# pich.net
KiCad netlist of a schematic drawn in EAGLE
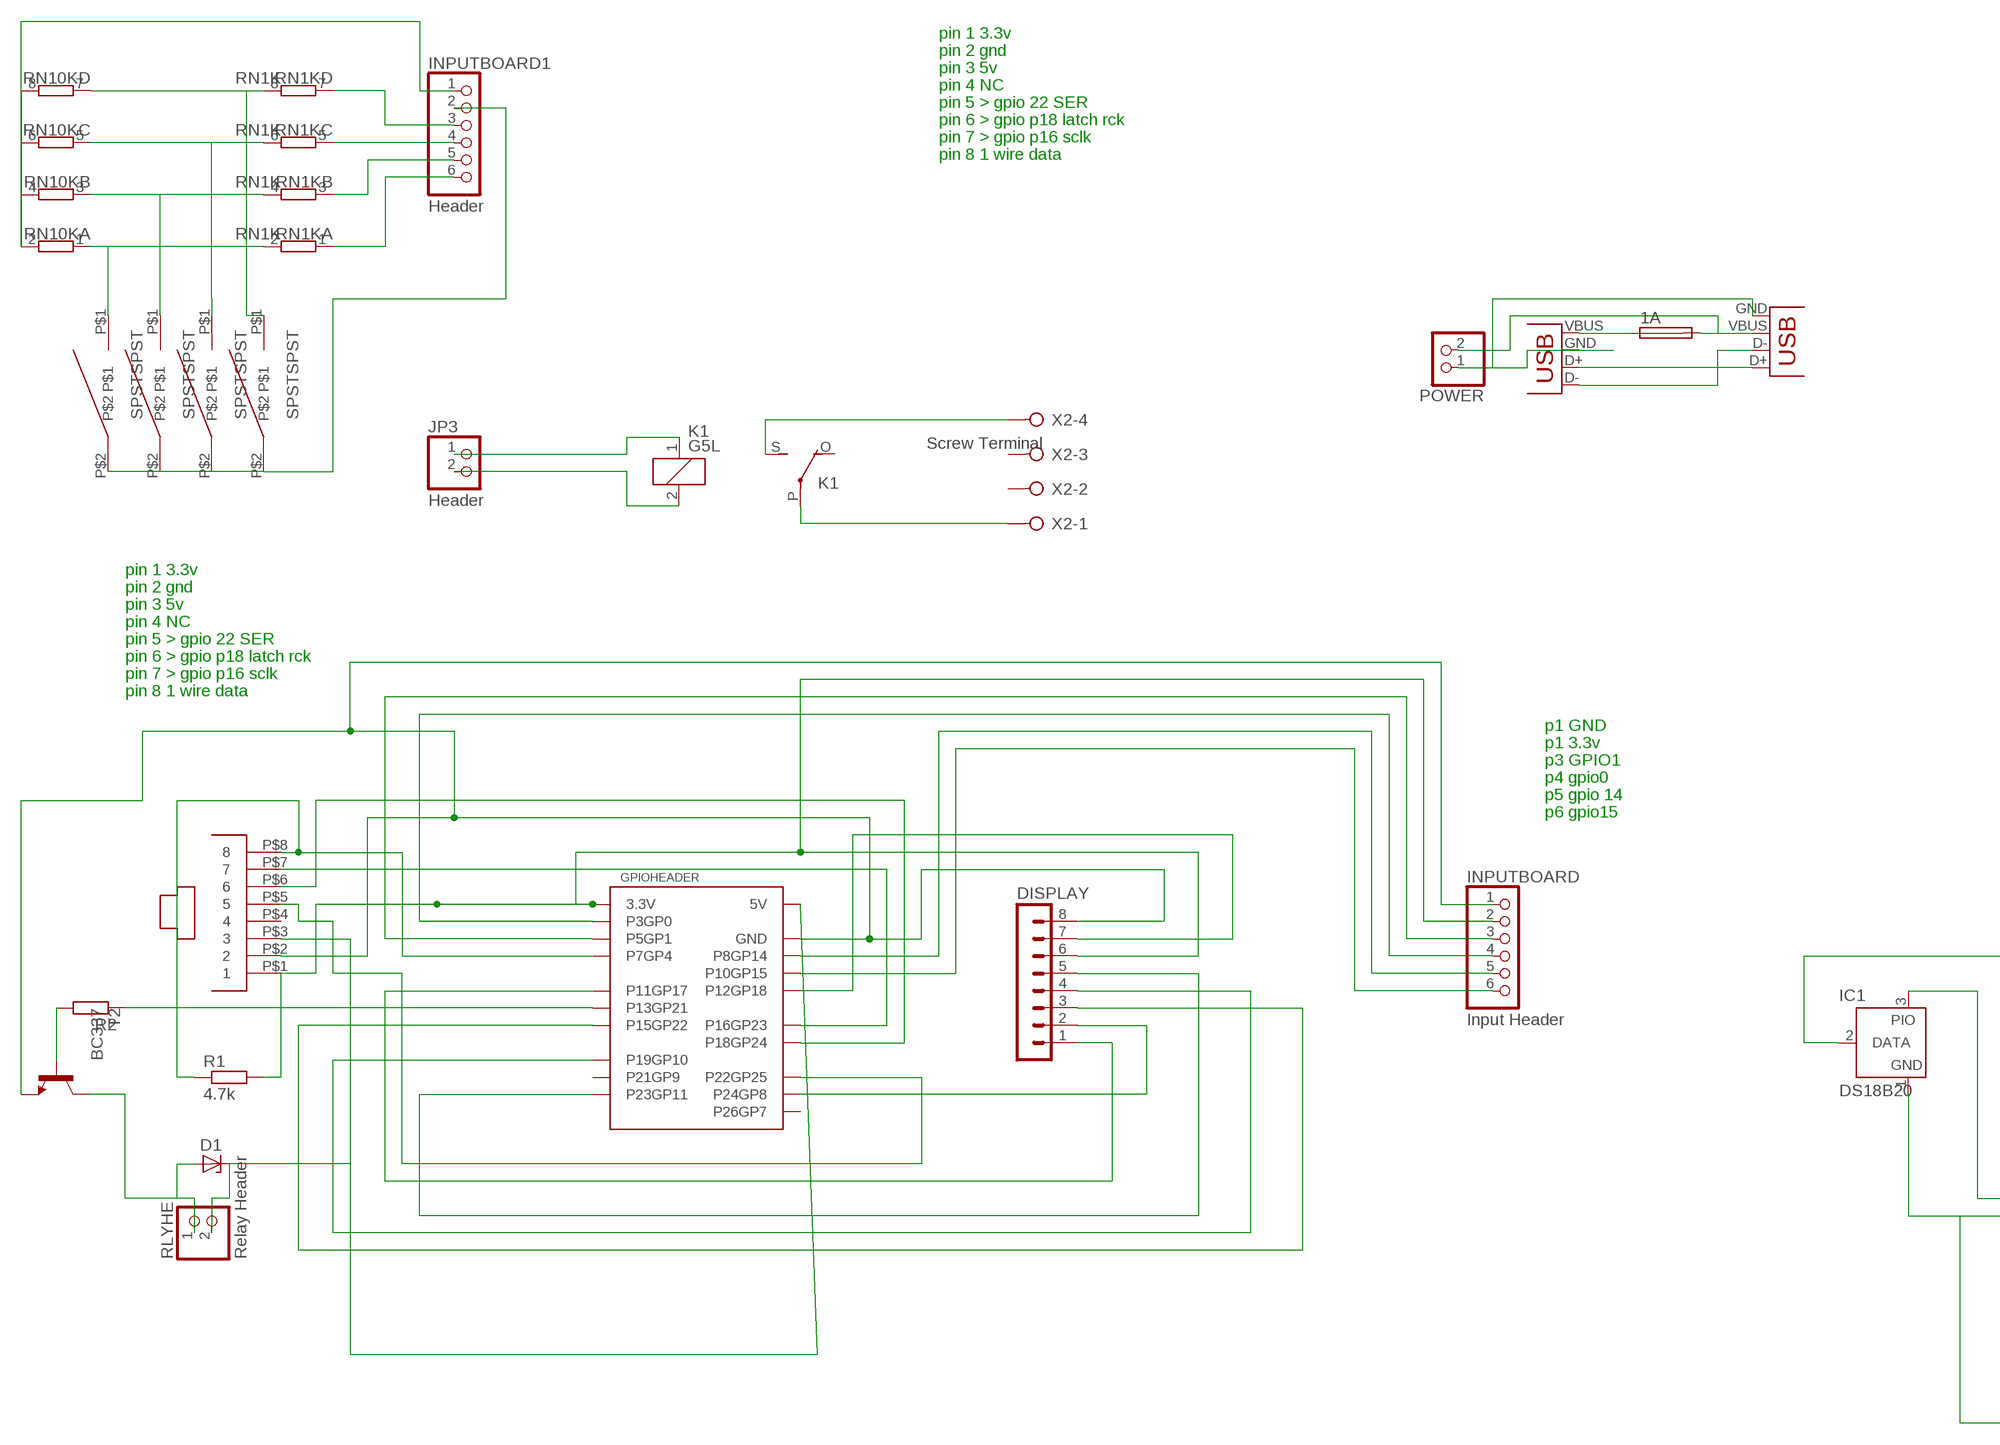
[diagram p0: schematic, sheet 1, part 1 of 2]
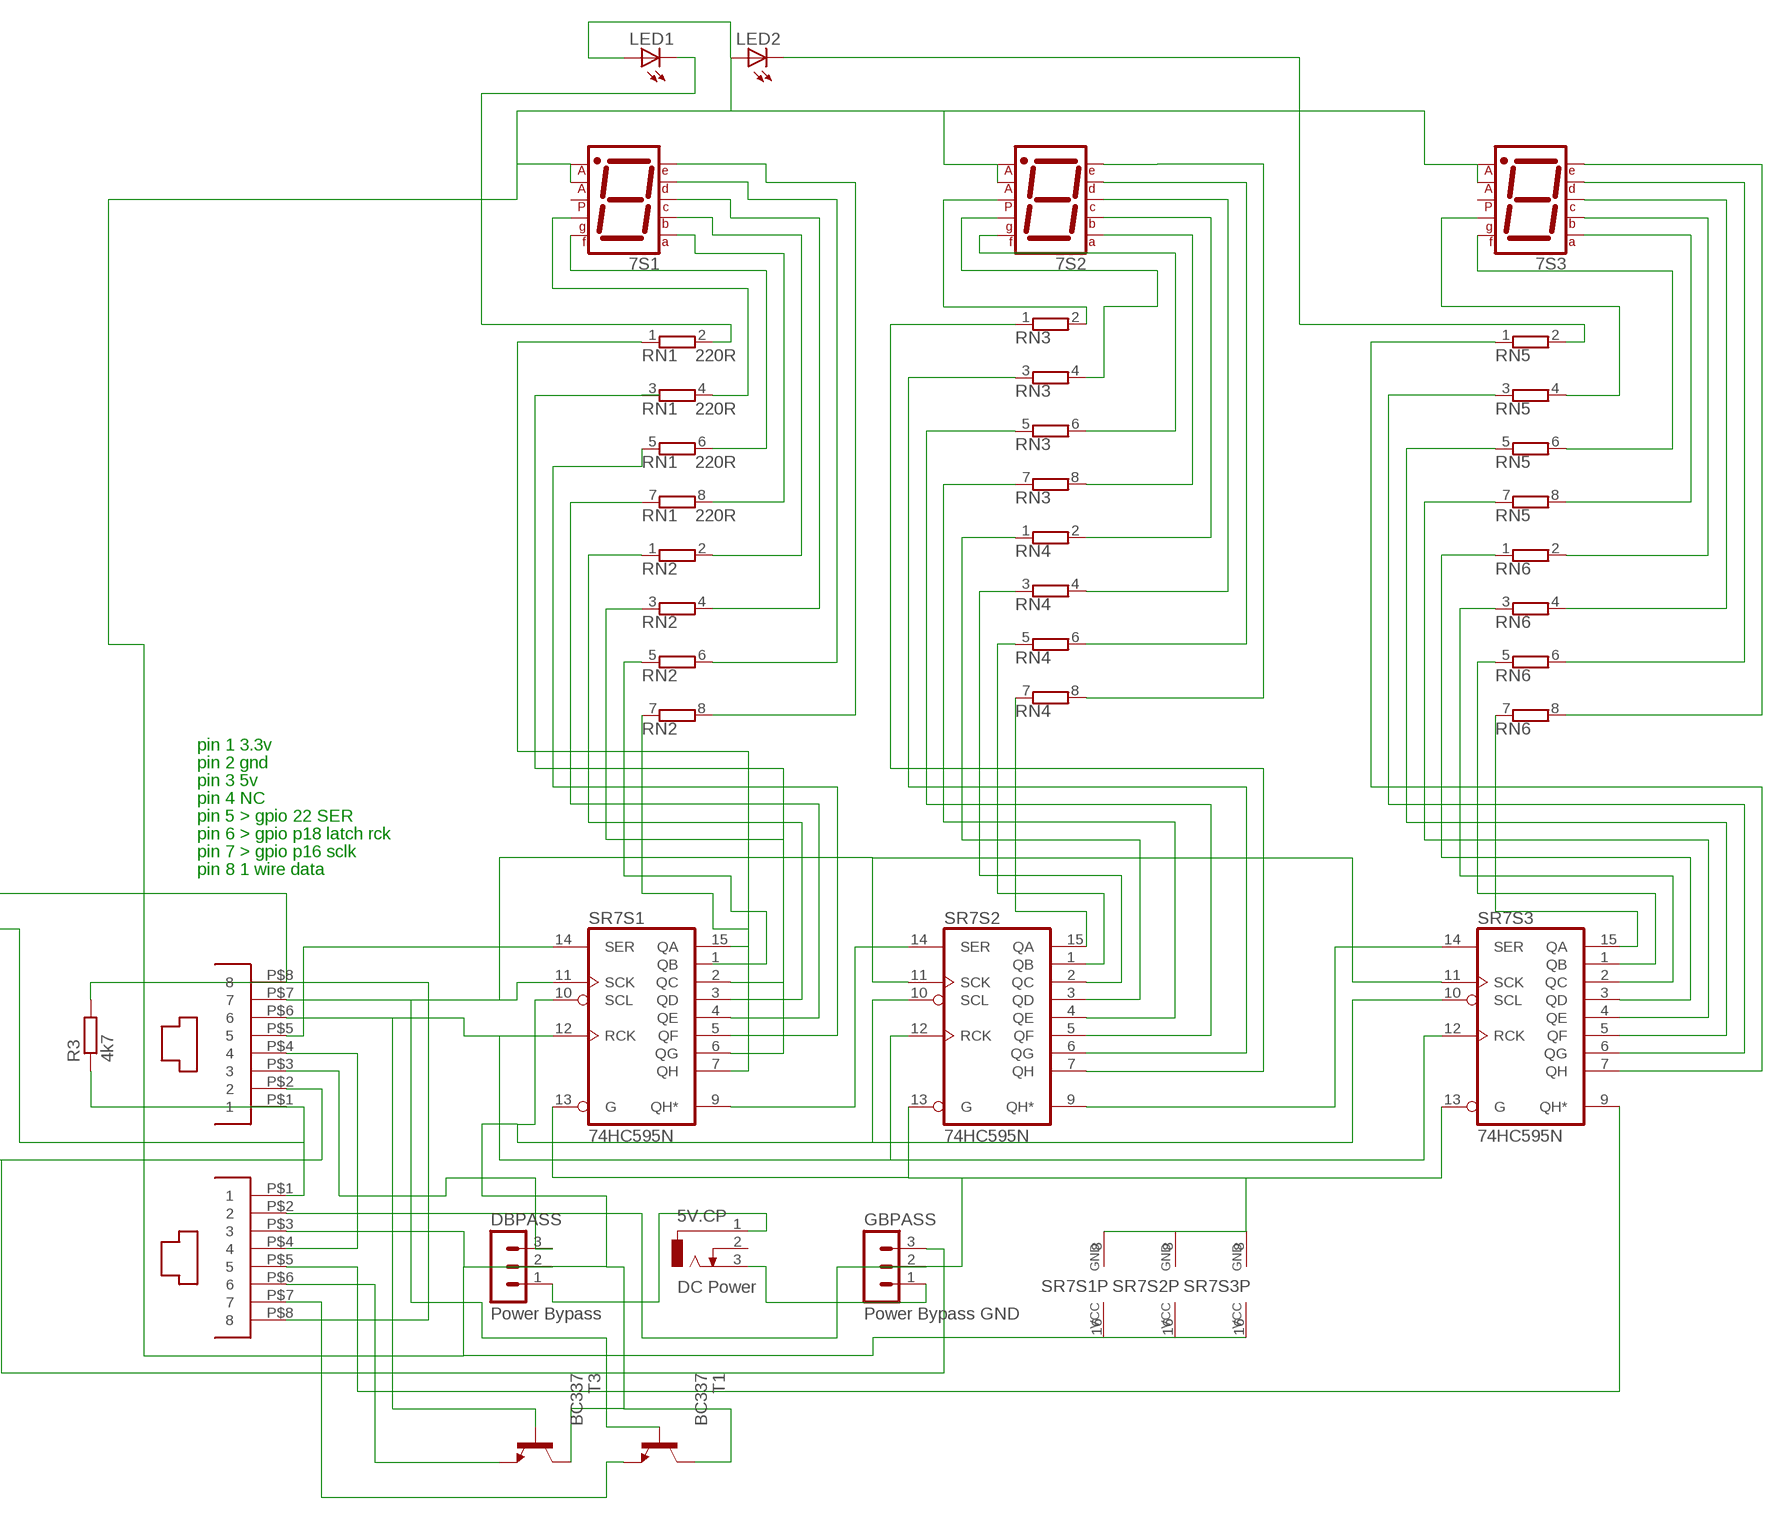
[diagram p1: schematic, sheet 1, part 2 of 2]

(export (version "E")
  (design (tool "Eeschema 10.0.6"))
  (components
    (comp (ref ".")
      (value "USB-A-H")
      (footprint "eagle-import:USB-A-H")
      (libsource (lib "eagle-import") (part "USB-A-H"))
    )
    (comp (ref "1A")
      (value "QPL")
      (footprint "eagle-import:QPL")
      (libsource (lib "eagle-import") (part "QPL"))
    )
    (comp (ref "5V.CP")
      (value "DC Power")
      (footprint "eagle-import:DCJ0303")
      (libsource (lib "eagle-import") (part "DCJ0303"))
    )
    (comp (ref "7S1")
      (value "7SEG-MCA")
      (footprint "eagle-import:7SEG-7")
      (libsource (lib "eagle-import") (part "7SEG-MCA"))
    )
    (comp (ref "7S2")
      (value "7SEG-MCA")
      (footprint "eagle-import:7SEG-7")
      (libsource (lib "eagle-import") (part "7SEG-MCA"))
    )
    (comp (ref "7S3")
      (value "7SEG-MCA")
      (footprint "eagle-import:7SEG-7")
      (libsource (lib "eagle-import") (part "7SEG-MCA"))
    )
    (comp (ref "D1")
      (value "1N821")
      (footprint "eagle-import:DO35Z10")
      (libsource (lib "eagle-import") (part "1N821"))
    )
    (comp (ref "DBPASS")
      (value "Power Bypass")
      (footprint "eagle-import:MA03-1")
      (libsource (lib "eagle-import") (part "MA03-1"))
    )
    (comp (ref "DISPLAY")
      (value "MA08-1")
      (footprint "eagle-import:MA08-1")
      (libsource (lib "eagle-import") (part "MA08-1"))
    )
    (comp (ref "GBPASS")
      (value "Power Bypass GND")
      (footprint "eagle-import:MA03-1")
      (libsource (lib "eagle-import") (part "MA03-1"))
    )
    (comp (ref "GPIOHEADER")
      (value "GPIOGPIOHEADER")
      (footprint "eagle-import:FE13-2")
      (libsource (lib "eagle-import") (part "GPIOGPIOHEADER"))
    )
    (comp (ref "IC1")
      (value "DS18B20")
      (footprint "eagle-import:TO92-")
      (fields (field (name "MF") "DALLAS SEMICONDUCTOR") (field (name "MPN") "DS2405"))
      (libsource (lib "eagle-import") (part "DS2405"))
    )
    (comp (ref "INPUTBOARD")
      (value "Input Header")
      (footprint "eagle-import:1X06")
      (libsource (lib "eagle-import") (part "PINHD-1X6"))
    )
    (comp (ref "INPUTBOARD1")
      (value "Header")
      (footprint "eagle-import:1X06")
      (libsource (lib "eagle-import") (part "PINHD-1X6"))
    )
    (comp (ref "INPUTHEADER")
      (value "ETHERNETTRUCONNECTRAPID")
      (footprint "eagle-import:ETHERNET")
      (libsource (lib "eagle-import") (part "ETHERNETTRUCONNECTRAPID"))
    )
    (comp (ref "JP3")
      (value "Header")
      (footprint "eagle-import:1X02")
      (libsource (lib "eagle-import") (part "PINHD-1X2"))
    )
    (comp (ref "K1")
      (value "G5L")
      (footprint "eagle-import:G5LE")
      (libsource (lib "eagle-import") (part "G5L"))
    )
    (comp (ref "LED1")
      (value "LED3MM")
      (footprint "eagle-import:LED3MM")
      (libsource (lib "eagle-import") (part "LED3MM"))
    )
    (comp (ref "LED2")
      (value "LED3MM")
      (footprint "eagle-import:LED3MM")
      (libsource (lib "eagle-import") (part "LED3MM"))
    )
    (comp (ref "OUTPUTHEADER")
      (value "ETHERNETTRUCONNECTRAPID")
      (footprint "eagle-import:ETHERNET")
      (libsource (lib "eagle-import") (part "ETHERNETTRUCONNECTRAPID"))
    )
    (comp (ref "POWER")
      (value "PINHD-1X2")
      (footprint "eagle-import:1X02")
      (libsource (lib "eagle-import") (part "PINHD-1X2"))
    )
    (comp (ref "R1")
      (value "4.7k")
      (footprint "eagle-import:0207_10")
      (libsource (lib "eagle-import") (part "R-EU_0207/10"))
    )
    (comp (ref "R2")
      (value "R-EU_0204/7")
      (footprint "eagle-import:0204_7")
      (libsource (lib "eagle-import") (part "R-EU_0204/7"))
    )
    (comp (ref "R3")
      (value "4k7")
      (footprint "eagle-import:0204V")
      (libsource (lib "eagle-import") (part "R-EU_0204/2V"))
    )
    (comp (ref "RLYHE")
      (value "Relay Header")
      (footprint "eagle-import:1X02")
      (libsource (lib "eagle-import") (part "PINHD-1X2"))
    )
    (comp (ref "RN1")
      (value "220R")
      (footprint "eagle-import:SIL8")
      (libsource (lib "eagle-import") (part "E4RP"))
    )
    (comp (ref "RN1K")
      (value "RN1K")
      (footprint "eagle-import:SIL8")
      (libsource (lib "eagle-import") (part "E4R"))
    )
    (comp (ref "RN2")
      (value "E4RP")
      (footprint "eagle-import:SIL8")
      (libsource (lib "eagle-import") (part "E4RP"))
    )
    (comp (ref "RN3")
      (value "E4RP")
      (footprint "eagle-import:SIL8")
      (libsource (lib "eagle-import") (part "E4RP"))
    )
    (comp (ref "RN4")
      (value "E4RP")
      (footprint "eagle-import:SIL8")
      (libsource (lib "eagle-import") (part "E4RP"))
    )
    (comp (ref "RN5")
      (value "E4RP")
      (footprint "eagle-import:SIL8")
      (libsource (lib "eagle-import") (part "E4RP"))
    )
    (comp (ref "RN6")
      (value "E4RP")
      (footprint "eagle-import:SIL8")
      (libsource (lib "eagle-import") (part "E4RP"))
    )
    (comp (ref "RN10K")
      (value "E4R")
      (footprint "eagle-import:SIL8")
      (libsource (lib "eagle-import") (part "E4R"))
    )
    (comp (ref "SR7S1")
      (value "74HC595N")
      (footprint "eagle-import:DIL16")
      (libsource (lib "eagle-import") (part "74595NHC"))
    )
    (comp (ref "SR7S2")
      (value "74HC595N")
      (footprint "eagle-import:DIL16")
      (libsource (lib "eagle-import") (part "74595NHC"))
    )
    (comp (ref "SR7S3")
      (value "74HC595N")
      (footprint "eagle-import:DIL16")
      (libsource (lib "eagle-import") (part "74595NHC"))
    )
    (comp (ref "T1")
      (value "BC337")
      (footprint "eagle-import:TO92")
      (libsource (lib "eagle-import") (part "BC337"))
    )
    (comp (ref "T2")
      (value "BC337")
      (footprint "eagle-import:TO92")
      (libsource (lib "eagle-import") (part "transistor-npn_BC337"))
    )
    (comp (ref "T3")
      (value "BC337")
      (footprint "eagle-import:TO92")
      (libsource (lib "eagle-import") (part "BC337"))
    )
    (comp (ref "THERMHEADER")
      (value "ETHERNETTRUCONNECTRAPID")
      (footprint "eagle-import:ETHERNET")
      (libsource (lib "eagle-import") (part "ETHERNETTRUCONNECTRAPID"))
    )
    (comp (ref "U$2")
      (value "SPSTSPST")
      (footprint "eagle-import:MAPLINSWITCH")
      (libsource (lib "eagle-import") (part "SPSTSPST"))
    )
    (comp (ref "U$3")
      (value "SPSTSPST")
      (footprint "eagle-import:MAPLINSWITCH")
      (libsource (lib "eagle-import") (part "SPSTSPST"))
    )
    (comp (ref "U$4")
      (value "SPSTSPST")
      (footprint "eagle-import:MAPLINSWITCH")
      (libsource (lib "eagle-import") (part "SPSTSPST"))
    )
    (comp (ref "U$5")
      (value "SPSTSPST")
      (footprint "eagle-import:MAPLINSWITCH")
      (libsource (lib "eagle-import") (part "SPSTSPST"))
    )
    (comp (ref "X1")
      (value "USB-A-HU")
      (footprint "eagle-import:USB-A-HU")
      (libsource (lib "eagle-import") (part "USB-A-HU"))
    )
    (comp (ref "X2")
      (value "Screw Terminal")
      (footprint "eagle-import:W237-4P")
      (libsource (lib "eagle-import") (part "W237-04P"))
    )
  )
  (nets
    (net (code "1") (name "Net-(.-D+)") (class "Default")
      (node (ref ".") (pin "D-") (pinfunction "D+_D-") (pintype "bidirectional"))
      (node (ref "X1") (pin "D-") (pinfunction "D-_D-") (pintype "bidirectional"))
    )
    (net (code "2") (name "Net-(.-D-)") (class "Default")
      (node (ref ".") (pin "D+") (pinfunction "D-_D+") (pintype "bidirectional"))
      (node (ref "X1") (pin "D+") (pinfunction "D+_D+") (pintype "bidirectional"))
    )
    (net (code "3") (name "Net-(.-GND)") (class "Default")
      (node (ref ".") (pin "VBUS") (pinfunction "GND_VBUS") (pintype "bidirectional"))
      (node (ref "1A") (pin "1") (pinfunction "1_1") (pintype "passive"))
    )
    (net (code "4") (name "Net-(.-VBUS)") (class "Default")
      (node (ref ".") (pin "GND") (pinfunction "VBUS_GND") (pintype "bidirectional"))
      (node (ref "POWER") (pin "1") (pinfunction "1_1") (pintype "passive"))
      (node (ref "X1") (pin "GND") (pinfunction "GND_GND") (pintype "bidirectional"))
    )
    (net (code "5") (name "Net-(1A-Pad2)") (class "Default")
      (node (ref "1A") (pin "2") (pinfunction "2_2") (pintype "passive"))
      (node (ref "POWER") (pin "2") (pinfunction "2_2") (pintype "passive"))
      (node (ref "X1") (pin "VBUS") (pinfunction "VBUS_VBUS") (pintype "bidirectional"))
    )
    (net (code "6") (name "Net-(5V.CP-Pad1)") (class "Default")
      (node (ref "5V.CP") (pin "1") (pinfunction "1_1") (pintype "passive"))
      (node (ref "DBPASS") (pin "1") (pinfunction "1_1") (pintype "passive"))
    )
    (net (code "7") (name "Net-(5V.CP-Pad3)") (class "Default")
      (node (ref "5V.CP") (pin "3") (pinfunction "3_3") (pintype "passive"))
      (node (ref "GBPASS") (pin "1") (pinfunction "1_1") (pintype "passive"))
    )
    (net (code "8") (name "Net-(7S1-A)") (class "Default")
      (node (ref "7S1") (pin "10") (pinfunction "A_10") (pintype "passive"))
      (node (ref "RN1") (pin "8") (pinfunction "2_8") (pintype "passive"))
    )
    (net (code "9") (name "Net-(7S1-B)") (class "Default")
      (node (ref "7S1") (pin "9") (pinfunction "B_9") (pintype "passive"))
      (node (ref "RN2") (pin "2") (pinfunction "2_2") (pintype "passive"))
    )
    (net (code "10") (name "Net-(7S1-C)") (class "Default")
      (node (ref "7S1") (pin "8") (pinfunction "C_8") (pintype "passive"))
      (node (ref "RN2") (pin "4") (pinfunction "2_4") (pintype "passive"))
    )
    (net (code "11") (name "Net-(7S1-CA1)") (class "Default")
      (node (ref "7S1") (pin "1") (pinfunction "CA1_1") (pintype "passive"))
      (node (ref "7S1") (pin "6") (pinfunction "CA2_6") (pintype "passive"))
      (node (ref "7S2") (pin "1") (pinfunction "CA1_1") (pintype "passive"))
      (node (ref "7S2") (pin "6") (pinfunction "CA2_6") (pintype "passive"))
      (node (ref "7S3") (pin "1") (pinfunction "CA1_1") (pintype "passive"))
      (node (ref "7S3") (pin "6") (pinfunction "CA2_6") (pintype "passive"))
      (node (ref "DBPASS") (pin "2") (pinfunction "2_2") (pintype "passive"))
      (node (ref "LED1") (pin "A") (pinfunction "A_A") (pintype "passive"))
      (node (ref "LED2") (pin "A") (pinfunction "A_A") (pintype "passive"))
      (node (ref "OUTPUTHEADER") (pin "P$3") (pinfunction "3_P$3") (pintype "bidirectional"))
      (node (ref "SR7S1") (pin "10") (pinfunction "SCL_10") (pintype "input"))
      (node (ref "SR7S1") (pin "16") (pinfunction "VCC_16") (pintype "power_in"))
      (node (ref "SR7S2") (pin "10") (pinfunction "SCL_10") (pintype "input"))
      (node (ref "SR7S2") (pin "16") (pinfunction "VCC_16") (pintype "power_in"))
      (node (ref "SR7S3") (pin "10") (pinfunction "SCL_10") (pintype "input"))
      (node (ref "SR7S3") (pin "16") (pinfunction "VCC_16") (pintype "power_in"))
      (node (ref "T1") (pin "3") (pinfunction "C_3") (pintype "passive"))
      (node (ref "T3") (pin "3") (pinfunction "C_3") (pintype "passive"))
    )
    (net (code "12") (name "Net-(7S1-D)") (class "Default")
      (node (ref "7S1") (pin "5") (pinfunction "D_5") (pintype "passive"))
      (node (ref "RN2") (pin "6") (pinfunction "2_6") (pintype "passive"))
    )
    (net (code "13") (name "Net-(7S1-E)") (class "Default")
      (node (ref "7S1") (pin "4") (pinfunction "E_4") (pintype "passive"))
      (node (ref "RN2") (pin "8") (pinfunction "2_8") (pintype "passive"))
    )
    (net (code "14") (name "Net-(7S1-F)") (class "Default")
      (node (ref "7S1") (pin "2") (pinfunction "F_2") (pintype "passive"))
      (node (ref "RN1") (pin "6") (pinfunction "2_6") (pintype "passive"))
    )
    (net (code "15") (name "Net-(7S1-G)") (class "Default")
      (node (ref "7S1") (pin "3") (pinfunction "G_3") (pintype "passive"))
      (node (ref "RN1") (pin "4") (pinfunction "2_4") (pintype "passive"))
    )
    (net (code "16") (name "Net-(7S2-A)") (class "Default")
      (node (ref "7S2") (pin "10") (pinfunction "A_10") (pintype "passive"))
      (node (ref "RN3") (pin "8") (pinfunction "2_8") (pintype "passive"))
    )
    (net (code "17") (name "Net-(7S2-B)") (class "Default")
      (node (ref "7S2") (pin "9") (pinfunction "B_9") (pintype "passive"))
      (node (ref "RN4") (pin "2") (pinfunction "2_2") (pintype "passive"))
    )
    (net (code "18") (name "Net-(7S2-C)") (class "Default")
      (node (ref "7S2") (pin "8") (pinfunction "C_8") (pintype "passive"))
      (node (ref "RN4") (pin "4") (pinfunction "2_4") (pintype "passive"))
    )
    (net (code "19") (name "Net-(7S2-D)") (class "Default")
      (node (ref "7S2") (pin "5") (pinfunction "D_5") (pintype "passive"))
      (node (ref "RN4") (pin "6") (pinfunction "2_6") (pintype "passive"))
    )
    (net (code "20") (name "Net-(7S2-DP)") (class "Default")
      (node (ref "7S2") (pin "7") (pinfunction "DP_7") (pintype "passive"))
      (node (ref "RN3") (pin "2") (pinfunction "2_2") (pintype "passive"))
    )
    (net (code "21") (name "Net-(7S2-E)") (class "Default")
      (node (ref "7S2") (pin "4") (pinfunction "E_4") (pintype "passive"))
      (node (ref "RN4") (pin "8") (pinfunction "2_8") (pintype "passive"))
    )
    (net (code "22") (name "Net-(7S2-F)") (class "Default")
      (node (ref "7S2") (pin "2") (pinfunction "F_2") (pintype "passive"))
      (node (ref "RN3") (pin "6") (pinfunction "2_6") (pintype "passive"))
    )
    (net (code "23") (name "Net-(7S2-G)") (class "Default")
      (node (ref "7S2") (pin "3") (pinfunction "G_3") (pintype "passive"))
      (node (ref "RN3") (pin "4") (pinfunction "2_4") (pintype "passive"))
    )
    (net (code "24") (name "Net-(7S3-A)") (class "Default")
      (node (ref "7S3") (pin "10") (pinfunction "A_10") (pintype "passive"))
      (node (ref "RN5") (pin "8") (pinfunction "2_8") (pintype "passive"))
    )
    (net (code "25") (name "Net-(7S3-B)") (class "Default")
      (node (ref "7S3") (pin "9") (pinfunction "B_9") (pintype "passive"))
      (node (ref "RN6") (pin "2") (pinfunction "2_2") (pintype "passive"))
    )
    (net (code "26") (name "Net-(7S3-C)") (class "Default")
      (node (ref "7S3") (pin "8") (pinfunction "C_8") (pintype "passive"))
      (node (ref "RN6") (pin "4") (pinfunction "2_4") (pintype "passive"))
    )
    (net (code "27") (name "Net-(7S3-D)") (class "Default")
      (node (ref "7S3") (pin "5") (pinfunction "D_5") (pintype "passive"))
      (node (ref "RN6") (pin "6") (pinfunction "2_6") (pintype "passive"))
    )
    (net (code "28") (name "Net-(7S3-E)") (class "Default")
      (node (ref "7S3") (pin "4") (pinfunction "E_4") (pintype "passive"))
      (node (ref "RN6") (pin "8") (pinfunction "2_8") (pintype "passive"))
    )
    (net (code "29") (name "Net-(7S3-F)") (class "Default")
      (node (ref "7S3") (pin "2") (pinfunction "F_2") (pintype "passive"))
      (node (ref "RN5") (pin "6") (pinfunction "2_6") (pintype "passive"))
    )
    (net (code "30") (name "Net-(7S3-G)") (class "Default")
      (node (ref "7S3") (pin "3") (pinfunction "G_3") (pintype "passive"))
      (node (ref "RN5") (pin "4") (pinfunction "2_4") (pintype "passive"))
    )
    (net (code "31") (name "Net-(GPIOHEADER-P3GP0)") (class "Default")
      (node (ref "GPIOHEADER") (pin "3") (pinfunction "P3GP0_3") (pintype "bidirectional"))
      (node (ref "INPUTBOARD") (pin "4") (pinfunction "4_4") (pintype "passive"))
    )
    (net (code "32") (name "Net-(GPIOHEADER-P5GP1)") (class "Default")
      (node (ref "GPIOHEADER") (pin "5") (pinfunction "P5GP1_5") (pintype "bidirectional"))
      (node (ref "INPUTBOARD") (pin "3") (pinfunction "3_3") (pintype "passive"))
    )
    (net (code "33") (name "Net-(GPIOHEADER-P7GP4)") (class "Default")
      (node (ref "GPIOHEADER") (pin "7") (pinfunction "P7GP4_7") (pintype "bidirectional"))
      (node (ref "R1") (pin "1") (pinfunction "1_1") (pintype "passive"))
      (node (ref "THERMHEADER") (pin "P$8") (pinfunction "8_P$8") (pintype "bidirectional"))
    )
    (net (code "34") (name "Net-(GPIOHEADER-P8GP14)") (class "Default")
      (node (ref "GPIOHEADER") (pin "8") (pinfunction "P8GP14_8") (pintype "bidirectional"))
      (node (ref "INPUTBOARD") (pin "5") (pinfunction "5_5") (pintype "passive"))
    )
    (net (code "35") (name "Net-(GPIOHEADER-P10GP15)") (class "Default")
      (node (ref "GPIOHEADER") (pin "10") (pinfunction "P10GP15_10") (pintype "bidirectional"))
      (node (ref "INPUTBOARD") (pin "6") (pinfunction "6_6") (pintype "passive"))
    )
    (net (code "36") (name "Net-(GPIOHEADER-P11GP17)") (class "Default")
      (node (ref "DISPLAY") (pin "1") (pinfunction "1_1") (pintype "passive"))
      (node (ref "GPIOHEADER") (pin "11") (pinfunction "P11GP17_11") (pintype "bidirectional"))
    )
    (net (code "37") (name "Net-(GPIOHEADER-P12GP18)") (class "Default")
      (node (ref "DISPLAY") (pin "7") (pinfunction "7_7") (pintype "passive"))
      (node (ref "GPIOHEADER") (pin "12") (pinfunction "P12GP18_12") (pintype "bidirectional"))
    )
    (net (code "38") (name "Net-(GPIOHEADER-P13GP21)") (class "Default")
      (node (ref "GPIOHEADER") (pin "13") (pinfunction "P13GP21_13") (pintype "bidirectional"))
      (node (ref "R2") (pin "1") (pinfunction "1_1") (pintype "passive"))
    )
    (net (code "39") (name "Net-(GPIOHEADER-P15GP22)") (class "Default")
      (node (ref "DISPLAY") (pin "3") (pinfunction "3_3") (pintype "passive"))
      (node (ref "GPIOHEADER") (pin "15") (pinfunction "P15GP22_15") (pintype "bidirectional"))
    )
    (net (code "40") (name "Net-(GPIOHEADER-P16GP23)") (class "Default")
      (node (ref "GPIOHEADER") (pin "16") (pinfunction "P16GP23_16") (pintype "bidirectional"))
      (node (ref "THERMHEADER") (pin "P$7") (pinfunction "7_P$7") (pintype "bidirectional"))
    )
    (net (code "41") (name "Net-(GPIOHEADER-P18GP24)") (class "Default")
      (node (ref "GPIOHEADER") (pin "18") (pinfunction "P18GP24_18") (pintype "bidirectional"))
      (node (ref "THERMHEADER") (pin "P$6") (pinfunction "6_P$6") (pintype "bidirectional"))
    )
    (net (code "42") (name "Net-(GPIOHEADER-P19GP10)") (class "Default")
      (node (ref "DISPLAY") (pin "4") (pinfunction "4_4") (pintype "passive"))
      (node (ref "GPIOHEADER") (pin "19") (pinfunction "P19GP10_19") (pintype "bidirectional"))
    )
    (net (code "43") (name "Net-(GPIOHEADER-P22GP25)") (class "Default")
      (node (ref "GPIOHEADER") (pin "22") (pinfunction "P22GP25_22") (pintype "bidirectional"))
      (node (ref "THERMHEADER") (pin "P$5") (pinfunction "5_P$5") (pintype "bidirectional"))
    )
    (net (code "44") (name "Net-(GPIOHEADER-P23GP11)") (class "Default")
      (node (ref "DISPLAY") (pin "5") (pinfunction "5_5") (pintype "passive"))
      (node (ref "GPIOHEADER") (pin "23") (pinfunction "P23GP11_23") (pintype "bidirectional"))
    )
    (net (code "45") (name "Net-(GPIOHEADER-P24GP8)") (class "Default")
      (node (ref "DISPLAY") (pin "2") (pinfunction "2_2") (pintype "passive"))
      (node (ref "GPIOHEADER") (pin "24") (pinfunction "P24GP8_24") (pintype "bidirectional"))
    )
    (net (code "46") (name "Net-(IC1-DATA)") (class "Default")
      (node (ref "IC1") (pin "2") (pinfunction "DATA_2") (pintype "input"))
      (node (ref "INPUTHEADER") (pin "P$8") (pinfunction "8_P$8") (pintype "bidirectional"))
      (node (ref "OUTPUTHEADER") (pin "P$8") (pinfunction "8_P$8") (pintype "bidirectional"))
      (node (ref "R3") (pin "2") (pinfunction "2_2") (pintype "passive"))
    )
    (net (code "47") (name "Net-(IC1-GND)") (class "Default")
      (node (ref "GBPASS") (pin "3") (pinfunction "3_3") (pintype "passive"))
      (node (ref "IC1") (pin "1") (pinfunction "GND_1") (pintype "passive"))
      (node (ref "INPUTHEADER") (pin "P$2") (pinfunction "2_P$2") (pintype "bidirectional"))
    )
    (net (code "48") (name "Net-(IC1-PIO)") (class "Default")
      (node (ref "IC1") (pin "3") (pinfunction "PIO_3") (pintype "passive"))
      (node (ref "INPUTHEADER") (pin "P$1") (pinfunction "1_P$1") (pintype "bidirectional"))
      (node (ref "OUTPUTHEADER") (pin "P$1") (pinfunction "1_P$1") (pintype "bidirectional"))
      (node (ref "R3") (pin "1") (pinfunction "1_1") (pintype "passive"))
    )
    (net (code "49") (name "Net-(INPUTBOARD1-Pad2)") (class "Default")
      (node (ref "INPUTBOARD1") (pin "2") (pinfunction "2_2") (pintype "passive"))
      (node (ref "U$2") (pin "P$2") (pinfunction "P$2_P$2") (pintype "bidirectional"))
      (node (ref "U$3") (pin "P$2") (pinfunction "P$2_P$2") (pintype "bidirectional"))
      (node (ref "U$4") (pin "P$2") (pinfunction "P$2_P$2") (pintype "bidirectional"))
      (node (ref "U$5") (pin "P$2") (pinfunction "P$2_P$2") (pintype "bidirectional"))
    )
    (net (code "50") (name "Net-(INPUTBOARD1-Pad6)") (class "Default")
      (node (ref "INPUTBOARD1") (pin "6") (pinfunction "6_6") (pintype "passive"))
      (node (ref "RN1K") (pin "1") (pinfunction "1_1") (pintype "passive"))
    )
    (net (code "51") (name "Net-(INPUTHEADER-3)") (class "Default")
      (node (ref "DBPASS") (pin "3") (pinfunction "3_3") (pintype "passive"))
      (node (ref "INPUTHEADER") (pin "P$3") (pinfunction "3_P$3") (pintype "bidirectional"))
    )
    (net (code "52") (name "Net-(INPUTHEADER-4)") (class "Default")
      (node (ref "INPUTHEADER") (pin "P$4") (pinfunction "4_P$4") (pintype "bidirectional"))
      (node (ref "OUTPUTHEADER") (pin "P$4") (pinfunction "4_P$4") (pintype "bidirectional"))
    )
    (net (code "53") (name "Net-(INPUTHEADER-5)") (class "Default")
      (node (ref "INPUTHEADER") (pin "P$5") (pinfunction "5_P$5") (pintype "bidirectional"))
      (node (ref "SR7S1") (pin "14") (pinfunction "SER_14") (pintype "input"))
    )
    (net (code "54") (name "Net-(INPUTHEADER-6)") (class "Default")
      (node (ref "INPUTHEADER") (pin "P$6") (pinfunction "6_P$6") (pintype "bidirectional"))
      (node (ref "SR7S1") (pin "12") (pinfunction "RCK_12") (pintype "input"))
      (node (ref "SR7S2") (pin "12") (pinfunction "RCK_12") (pintype "input"))
      (node (ref "SR7S3") (pin "12") (pinfunction "RCK_12") (pintype "input"))
      (node (ref "T3") (pin "2") (pinfunction "B_2") (pintype "passive"))
    )
    (net (code "55") (name "Net-(INPUTHEADER-7)") (class "Default")
      (node (ref "INPUTHEADER") (pin "P$7") (pinfunction "7_P$7") (pintype "bidirectional"))
      (node (ref "SR7S1") (pin "11") (pinfunction "SCK_11") (pintype "input"))
      (node (ref "SR7S2") (pin "11") (pinfunction "SCK_11") (pintype "input"))
      (node (ref "SR7S3") (pin "11") (pinfunction "SCK_11") (pintype "input"))
      (node (ref "T1") (pin "2") (pinfunction "B_2") (pintype "passive"))
    )
    (net (code "56") (name "Net-(JP3-Pad1)") (class "Default")
      (node (ref "JP3") (pin "1") (pinfunction "1_1") (pintype "passive"))
      (node (ref "K1") (pin "1") (pinfunction "1_1") (pintype "passive"))
    )
    (net (code "57") (name "Net-(JP3-Pad2)") (class "Default")
      (node (ref "JP3") (pin "2") (pinfunction "2_2") (pintype "passive"))
      (node (ref "K1") (pin "2") (pinfunction "2_2") (pintype "passive"))
    )
    (net (code "58") (name "Net-(LED1-C)") (class "Default")
      (node (ref "LED1") (pin "K") (pinfunction "C_K") (pintype "passive"))
      (node (ref "RN1") (pin "2") (pinfunction "2_2") (pintype "passive"))
    )
    (net (code "59") (name "Net-(LED2-C)") (class "Default")
      (node (ref "LED2") (pin "K") (pinfunction "C_K") (pintype "passive"))
      (node (ref "RN5") (pin "2") (pinfunction "2_2") (pintype "passive"))
    )
    (net (code "60") (name "Net-(OUTPUTHEADER-2)") (class "Default")
      (node (ref "GBPASS") (pin "2") (pinfunction "2_2") (pintype "passive"))
      (node (ref "OUTPUTHEADER") (pin "P$2") (pinfunction "2_P$2") (pintype "bidirectional"))
      (node (ref "SR7S1") (pin "13") (pinfunction "G_13") (pintype "input"))
      (node (ref "SR7S1") (pin "8") (pinfunction "GND_8") (pintype "power_in"))
      (node (ref "SR7S2") (pin "13") (pinfunction "G_13") (pintype "input"))
      (node (ref "SR7S2") (pin "8") (pinfunction "GND_8") (pintype "power_in"))
      (node (ref "SR7S3") (pin "13") (pinfunction "G_13") (pintype "input"))
      (node (ref "SR7S3") (pin "8") (pinfunction "GND_8") (pintype "power_in"))
    )
    (net (code "61") (name "Net-(OUTPUTHEADER-5)") (class "Default")
      (node (ref "OUTPUTHEADER") (pin "P$5") (pinfunction "5_P$5") (pintype "bidirectional"))
      (node (ref "SR7S3") (pin "9") (pinfunction "QH*_9") (pintype "tri_state"))
    )
    (net (code "62") (name "Net-(OUTPUTHEADER-6)") (class "Default")
      (node (ref "OUTPUTHEADER") (pin "P$6") (pinfunction "6_P$6") (pintype "bidirectional"))
      (node (ref "T3") (pin "1") (pinfunction "E_1") (pintype "passive"))
    )
    (net (code "63") (name "Net-(OUTPUTHEADER-7)") (class "Default")
      (node (ref "OUTPUTHEADER") (pin "P$7") (pinfunction "7_P$7") (pintype "bidirectional"))
      (node (ref "T1") (pin "1") (pinfunction "E_1") (pintype "passive"))
    )
    (net (code "64") (name "Net-(RN1B-1)") (class "Default")
      (node (ref "RN1") (pin "3") (pinfunction "1_3") (pintype "passive"))
      (node (ref "SR7S1") (pin "6") (pinfunction "QG_6") (pintype "tri_state"))
    )
    (net (code "65") (name "Net-(RN1C-1)") (class "Default")
      (node (ref "RN1") (pin "5") (pinfunction "1_5") (pintype "passive"))
      (node (ref "SR7S1") (pin "5") (pinfunction "QF_5") (pintype "tri_state"))
    )
    (net (code "66") (name "Net-(RN1D-1)") (class "Default")
      (node (ref "RN1") (pin "7") (pinfunction "1_7") (pintype "passive"))
      (node (ref "SR7S1") (pin "4") (pinfunction "QE_4") (pintype "tri_state"))
    )
    (net (code "67") (name "Net-(RN1KB-1)") (class "Default")
      (node (ref "INPUTBOARD1") (pin "5") (pinfunction "5_5") (pintype "passive"))
      (node (ref "RN1K") (pin "3") (pinfunction "1_3") (pintype "passive"))
    )
    (net (code "68") (name "Net-(RN1KC-1)") (class "Default")
      (node (ref "INPUTBOARD1") (pin "4") (pinfunction "4_4") (pintype "passive"))
      (node (ref "RN1K") (pin "5") (pinfunction "1_5") (pintype "passive"))
    )
    (net (code "69") (name "Net-(RN1KD-1)") (class "Default")
      (node (ref "INPUTBOARD1") (pin "3") (pinfunction "3_3") (pintype "passive"))
      (node (ref "RN1K") (pin "7") (pinfunction "1_7") (pintype "passive"))
    )
    (net (code "70") (name "Net-(RN2B-1)") (class "Default")
      (node (ref "RN2") (pin "3") (pinfunction "1_3") (pintype "passive"))
      (node (ref "SR7S1") (pin "2") (pinfunction "QC_2") (pintype "tri_state"))
    )
    (net (code "71") (name "Net-(RN2C-1)") (class "Default")
      (node (ref "RN2") (pin "5") (pinfunction "1_5") (pintype "passive"))
      (node (ref "SR7S1") (pin "1") (pinfunction "QB_1") (pintype "tri_state"))
    )
    (net (code "72") (name "Net-(RN2D-1)") (class "Default")
      (node (ref "RN2") (pin "7") (pinfunction "1_7") (pintype "passive"))
      (node (ref "SR7S1") (pin "15") (pinfunction "QA_15") (pintype "tri_state"))
    )
    (net (code "73") (name "Net-(RN3B-1)") (class "Default")
      (node (ref "RN3") (pin "3") (pinfunction "1_3") (pintype "passive"))
      (node (ref "SR7S2") (pin "6") (pinfunction "QG_6") (pintype "tri_state"))
    )
    (net (code "74") (name "Net-(RN3C-1)") (class "Default")
      (node (ref "RN3") (pin "5") (pinfunction "1_5") (pintype "passive"))
      (node (ref "SR7S2") (pin "5") (pinfunction "QF_5") (pintype "tri_state"))
    )
    (net (code "75") (name "Net-(RN3D-1)") (class "Default")
      (node (ref "RN3") (pin "7") (pinfunction "1_7") (pintype "passive"))
      (node (ref "SR7S2") (pin "4") (pinfunction "QE_4") (pintype "tri_state"))
    )
    (net (code "76") (name "Net-(RN4B-1)") (class "Default")
      (node (ref "RN4") (pin "3") (pinfunction "1_3") (pintype "passive"))
      (node (ref "SR7S2") (pin "2") (pinfunction "QC_2") (pintype "tri_state"))
    )
    (net (code "77") (name "Net-(RN4C-1)") (class "Default")
      (node (ref "RN4") (pin "5") (pinfunction "1_5") (pintype "passive"))
      (node (ref "SR7S2") (pin "1") (pinfunction "QB_1") (pintype "tri_state"))
    )
    (net (code "78") (name "Net-(RN4D-1)") (class "Default")
      (node (ref "RN4") (pin "7") (pinfunction "1_7") (pintype "passive"))
      (node (ref "SR7S2") (pin "15") (pinfunction "QA_15") (pintype "tri_state"))
    )
    (net (code "79") (name "Net-(RN5B-1)") (class "Default")
      (node (ref "RN5") (pin "3") (pinfunction "1_3") (pintype "passive"))
      (node (ref "SR7S3") (pin "6") (pinfunction "QG_6") (pintype "tri_state"))
    )
    (net (code "80") (name "Net-(RN5C-1)") (class "Default")
      (node (ref "RN5") (pin "5") (pinfunction "1_5") (pintype "passive"))
      (node (ref "SR7S3") (pin "5") (pinfunction "QF_5") (pintype "tri_state"))
    )
    (net (code "81") (name "Net-(RN5D-1)") (class "Default")
      (node (ref "RN5") (pin "7") (pinfunction "1_7") (pintype "passive"))
      (node (ref "SR7S3") (pin "4") (pinfunction "QE_4") (pintype "tri_state"))
    )
    (net (code "82") (name "Net-(RN6B-1)") (class "Default")
      (node (ref "RN6") (pin "3") (pinfunction "1_3") (pintype "passive"))
      (node (ref "SR7S3") (pin "2") (pinfunction "QC_2") (pintype "tri_state"))
    )
    (net (code "83") (name "Net-(RN6C-1)") (class "Default")
      (node (ref "RN6") (pin "5") (pinfunction "1_5") (pintype "passive"))
      (node (ref "SR7S3") (pin "1") (pinfunction "QB_1") (pintype "tri_state"))
    )
    (net (code "84") (name "Net-(RN6D-1)") (class "Default")
      (node (ref "RN6") (pin "7") (pinfunction "1_7") (pintype "passive"))
      (node (ref "SR7S3") (pin "15") (pinfunction "QA_15") (pintype "tri_state"))
    )
    (net (code "85") (name "Net-(RN10K-Pad1)") (class "Default")
      (node (ref "RN10K") (pin "1") (pinfunction "1_1") (pintype "passive"))
      (node (ref "RN1K") (pin "2") (pinfunction "2_2") (pintype "passive"))
      (node (ref "U$2") (pin "P$1") (pinfunction "P$1_P$1") (pintype "bidirectional"))
    )
    (net (code "86") (name "Net-(RN10KB-1)") (class "Default")
      (node (ref "RN10K") (pin "3") (pinfunction "1_3") (pintype "passive"))
      (node (ref "RN1K") (pin "4") (pinfunction "2_4") (pintype "passive"))
      (node (ref "U$3") (pin "P$1") (pinfunction "P$1_P$1") (pintype "bidirectional"))
    )
    (net (code "87") (name "Net-(RN10KB-2)") (class "Default")
      (node (ref "INPUTBOARD1") (pin "1") (pinfunction "1_1") (pintype "passive"))
      (node (ref "RN10K") (pin "2") (pinfunction "2_2") (pintype "passive"))
      (node (ref "RN10K") (pin "4") (pinfunction "2_4") (pintype "passive"))
      (node (ref "RN10K") (pin "6") (pinfunction "2_6") (pintype "passive"))
      (node (ref "RN10K") (pin "8") (pinfunction "2_8") (pintype "passive"))
    )
    (net (code "88") (name "Net-(RN10KC-1)") (class "Default")
      (node (ref "RN10K") (pin "5") (pinfunction "1_5") (pintype "passive"))
      (node (ref "RN1K") (pin "6") (pinfunction "2_6") (pintype "passive"))
      (node (ref "U$4") (pin "P$1") (pinfunction "P$1_P$1") (pintype "bidirectional"))
    )
    (net (code "89") (name "Net-(RN10KD-1)") (class "Default")
      (node (ref "RN10K") (pin "7") (pinfunction "1_7") (pintype "passive"))
      (node (ref "RN1K") (pin "8") (pinfunction "2_8") (pintype "passive"))
      (node (ref "U$5") (pin "P$1") (pinfunction "P$1_P$1") (pintype "bidirectional"))
    )
    (net (code "90") (name "Net-(SR7S1A-QD)") (class "Default")
      (node (ref "RN2") (pin "1") (pinfunction "1_1") (pintype "passive"))
      (node (ref "SR7S1") (pin "3") (pinfunction "QD_3") (pintype "tri_state"))
    )
    (net (code "91") (name "Net-(SR7S1A-QH)") (class "Default")
      (node (ref "RN1") (pin "1") (pinfunction "1_1") (pintype "passive"))
      (node (ref "SR7S1") (pin "7") (pinfunction "QH_7") (pintype "tri_state"))
    )
    (net (code "92") (name "Net-(SR7S1A-QH*)") (class "Default")
      (node (ref "SR7S1") (pin "9") (pinfunction "QH*_9") (pintype "tri_state"))
      (node (ref "SR7S2") (pin "14") (pinfunction "SER_14") (pintype "input"))
    )
    (net (code "93") (name "Net-(SR7S2A-QD)") (class "Default")
      (node (ref "RN4") (pin "1") (pinfunction "1_1") (pintype "passive"))
      (node (ref "SR7S2") (pin "3") (pinfunction "QD_3") (pintype "tri_state"))
    )
    (net (code "94") (name "Net-(SR7S2A-QH)") (class "Default")
      (node (ref "RN3") (pin "1") (pinfunction "1_1") (pintype "passive"))
      (node (ref "SR7S2") (pin "7") (pinfunction "QH_7") (pintype "tri_state"))
    )
    (net (code "95") (name "Net-(SR7S2A-QH*)") (class "Default")
      (node (ref "SR7S2") (pin "9") (pinfunction "QH*_9") (pintype "tri_state"))
      (node (ref "SR7S3") (pin "14") (pinfunction "SER_14") (pintype "input"))
    )
    (net (code "96") (name "Net-(SR7S3A-QD)") (class "Default")
      (node (ref "RN6") (pin "1") (pinfunction "1_1") (pintype "passive"))
      (node (ref "SR7S3") (pin "3") (pinfunction "QD_3") (pintype "tri_state"))
    )
    (net (code "97") (name "Net-(SR7S3A-QH)") (class "Default")
      (node (ref "RN5") (pin "1") (pinfunction "1_1") (pintype "passive"))
      (node (ref "SR7S3") (pin "7") (pinfunction "QH_7") (pintype "tri_state"))
    )
    (net (code "98") (name "Net-(T2-B)") (class "Default")
      (node (ref "R2") (pin "2") (pinfunction "2_2") (pintype "passive"))
      (node (ref "T2") (pin "2") (pinfunction "B_2") (pintype "passive"))
    )
    (net (code "99") (name "Net-(T2-C)") (class "Default")
      (node (ref "D1") (pin "A") (pinfunction "A_A") (pintype "passive"))
      (node (ref "RLYHE") (pin "1") (pinfunction "1_1") (pintype "passive"))
      (node (ref "T2") (pin "3") (pinfunction "C_3") (pintype "passive"))
    )
    (net (code "100") (name "Net-(T2-E)") (class "Default")
      (node (ref "DISPLAY") (pin "8") (pinfunction "8_8") (pintype "passive"))
      (node (ref "GPIOHEADER") (pin "14") (pinfunction "GND_14") (pintype "bidirectional"))
      (node (ref "GPIOHEADER") (pin "20") (pinfunction "GND_20") (pintype "bidirectional"))
      (node (ref "GPIOHEADER") (pin "25") (pinfunction "GND_25") (pintype "bidirectional"))
      (node (ref "GPIOHEADER") (pin "6") (pinfunction "GND_6") (pintype "bidirectional"))
      (node (ref "GPIOHEADER") (pin "9") (pinfunction "GND_9") (pintype "bidirectional"))
      (node (ref "INPUTBOARD") (pin "1") (pinfunction "1_1") (pintype "passive"))
      (node (ref "T2") (pin "1") (pinfunction "E_1") (pintype "passive"))
      (node (ref "THERMHEADER") (pin "P$2") (pinfunction "2_P$2") (pintype "bidirectional"))
    )
    (net (code "101") (name "Net-(THERMHEADER-1)") (class "Default")
      (node (ref "DISPLAY") (pin "6") (pinfunction "6_6") (pintype "passive"))
      (node (ref "GPIOHEADER") (pin "1") (pinfunction "3.3V_1") (pintype "bidirectional"))
      (node (ref "GPIOHEADER") (pin "17") (pinfunction "3.3V_17") (pintype "bidirectional"))
      (node (ref "INPUTBOARD") (pin "2") (pinfunction "2_2") (pintype "passive"))
      (node (ref "R1") (pin "2") (pinfunction "2_2") (pintype "passive"))
      (node (ref "THERMHEADER") (pin "P$1") (pinfunction "1_P$1") (pintype "bidirectional"))
    )
    (net (code "102") (name "Net-(THERMHEADER-3)") (class "Default")
      (node (ref "D1") (pin "C") (pinfunction "C_C") (pintype "passive"))
      (node (ref "GPIOHEADER") (pin "2") (pinfunction "5V_2") (pintype "bidirectional"))
      (node (ref "GPIOHEADER") (pin "4") (pinfunction "5V_4") (pintype "bidirectional"))
      (node (ref "RLYHE") (pin "2") (pinfunction "2_2") (pintype "passive"))
      (node (ref "THERMHEADER") (pin "P$3") (pinfunction "3_P$3") (pintype "bidirectional"))
    )
    (net (code "103") (name "Net-(X2A-KL)") (class "Default")
      (node (ref "K1") (pin "P") (pinfunction "P_P") (pintype "passive"))
      (node (ref "X2") (pin "1") (pinfunction "KL_1") (pintype "passive"))
    )
    (net (code "104") (name "Net-(X2D-KL)") (class "Default")
      (node (ref "K1") (pin "S") (pinfunction "S_S") (pintype "passive"))
      (node (ref "X2") (pin "4") (pinfunction "KL_4") (pintype "passive"))
    )
    (net (code "105") (name "unconnected-(5V.CP-Pad2)") (class "Default")
      (node (ref "5V.CP") (pin "2") (pinfunction "2_2") (pintype "passive"))
    )
    (net (code "106") (name "unconnected-(7S1-DP-Pad7)") (class "Default")
      (node (ref "7S1") (pin "7") (pinfunction "DP_7") (pintype "passive"))
    )
    (net (code "107") (name "unconnected-(7S3-DP-Pad7)") (class "Default")
      (node (ref "7S3") (pin "7") (pinfunction "DP_7") (pintype "passive"))
    )
    (net (code "108") (name "unconnected-(GPIOHEADER-P21GP9-Pad21)") (class "Default")
      (node (ref "GPIOHEADER") (pin "21") (pinfunction "P21GP9_21") (pintype "bidirectional"))
    )
    (net (code "109") (name "unconnected-(GPIOHEADER-P26GP7-Pad26)") (class "Default")
      (node (ref "GPIOHEADER") (pin "26") (pinfunction "P26GP7_26") (pintype "bidirectional"))
    )
    (net (code "110") (name "unconnected-(K1-PadO)") (class "Default")
      (node (ref "K1") (pin "O") (pinfunction "O_O") (pintype "passive"))
    )
    (net (code "111") (name "unconnected-(THERMHEADER-4-PadP$4)") (class "Default")
      (node (ref "THERMHEADER") (pin "P$4") (pinfunction "4_P$4") (pintype "bidirectional"))
    )
    (net (code "112") (name "unconnected-(X2B-KL-Pad2)") (class "Default")
      (node (ref "X2") (pin "2") (pinfunction "KL_2") (pintype "passive"))
    )
    (net (code "113") (name "unconnected-(X2C-KL-Pad3)") (class "Default")
      (node (ref "X2") (pin "3") (pinfunction "KL_3") (pintype "passive"))
    )
  )
)
